# config-bank2.net
KiCad netlist of a schematic drawn in Altium Designer
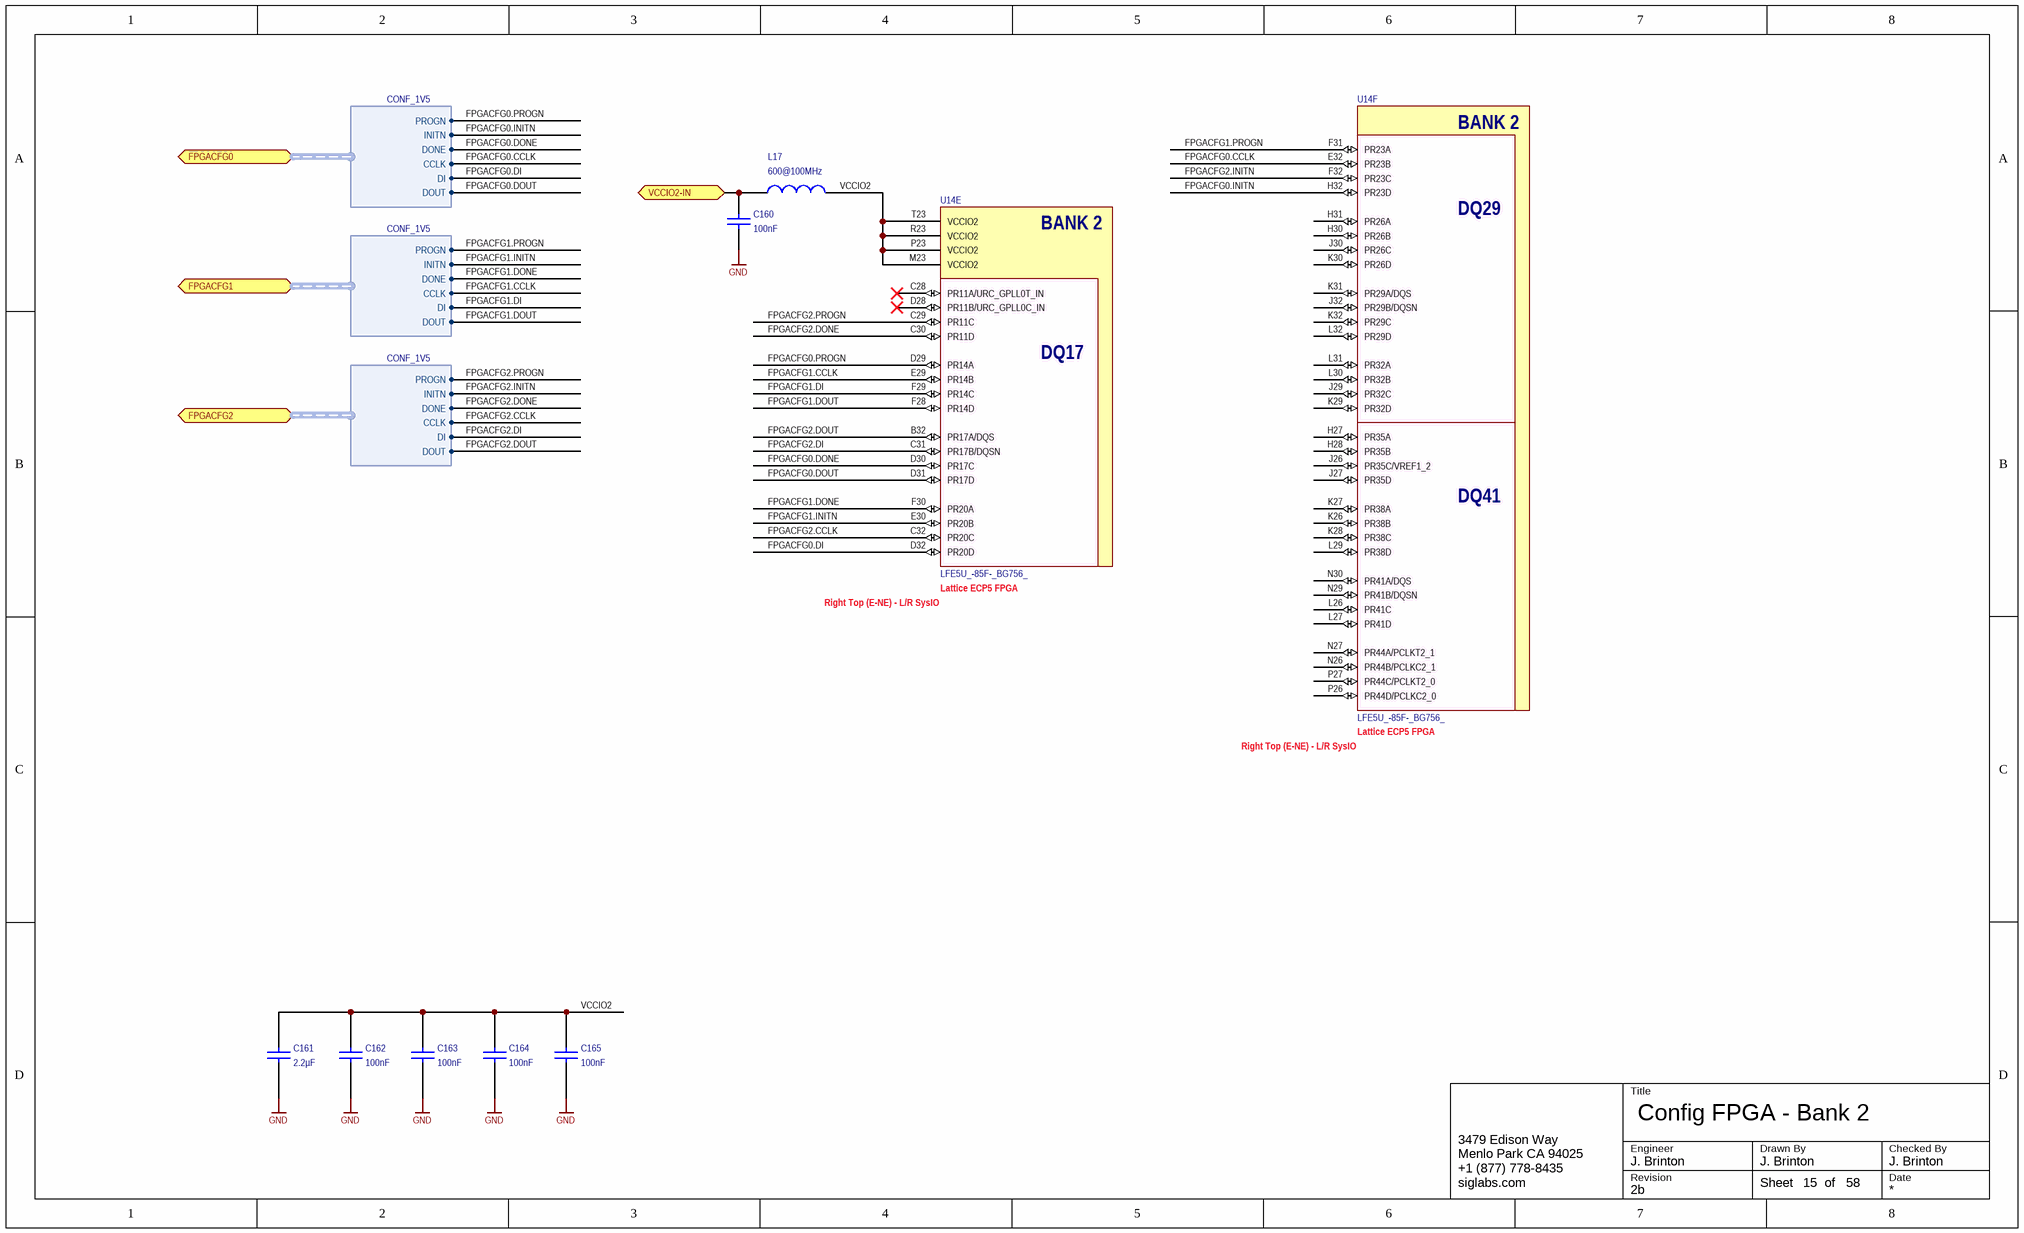
[diagram p0: config-bank2.SchDoc]

(export (version "E")
  (design (tool "Eeschema 10.0.6"))
  (components
    (comp (ref "C160")
      (value "100nF")
      (footprint "generic:CAPC1005X56N")
      (description "Ceramic Capacitor 100nF ±10% 16V X7R 0402")
      (fields (field (name "MANUFACTURER") "Murata") (field (name "TOLERANCE") "±10%"))
      (libsource (lib "murata") (part "GRM155R71A104KA01J"))
    )
    (comp (ref "C161")
      (value "2.2µF")
      (footprint "generic:CAPC1608X90N")
      (description "Ceramic Capacitor 2.2uF ±10% 10V X7R 0603")
      (fields (field (name "MANUFACTURER") "Murata") (field (name "TOLERANCE") "±10%"))
      (libsource (lib "murata") (part "GRM188R71A225KE15D"))
    )
    (comp (ref "C162")
      (value "100nF")
      (footprint "generic:CAPC1005X56N")
      (description "Ceramic Capacitor 100nF ±10% 16V X7R 0402")
      (fields (field (name "MANUFACTURER") "Murata") (field (name "TOLERANCE") "±10%"))
      (libsource (lib "murata") (part "GRM155R71A104KA01J"))
    )
    (comp (ref "C163")
      (value "100nF")
      (footprint "generic:CAPC1005X56N")
      (description "Ceramic Capacitor 100nF ±10% 16V X7R 0402")
      (fields (field (name "MANUFACTURER") "Murata") (field (name "TOLERANCE") "±10%"))
      (libsource (lib "murata") (part "GRM155R71A104KA01J"))
    )
    (comp (ref "C164")
      (value "100nF")
      (footprint "generic:CAPC1005X56N")
      (description "Ceramic Capacitor 100nF ±10% 16V X7R 0402")
      (fields (field (name "MANUFACTURER") "Murata") (field (name "TOLERANCE") "±10%"))
      (libsource (lib "murata") (part "GRM155R71A104KA01J"))
    )
    (comp (ref "C165")
      (value "100nF")
      (footprint "generic:CAPC1005X56N")
      (description "Ceramic Capacitor 100nF ±10% 16V X7R 0402")
      (fields (field (name "MANUFACTURER") "Murata") (field (name "TOLERANCE") "±10%"))
      (libsource (lib "murata") (part "GRM155R71A104KA01J"))
    )
    (comp (ref "L17")
      (value "600@100MHz")
      (footprint "0402")
      (description "Ferrite Bead 600-Ohm @ 100MHz 900mA 0402")
      (fields (field (name "MANUFACTURER") "Murata") (field (name "TOLERANCE") "±25%"))
      (libsource (lib "Graviton") (part "IND 0402"))
    )
    (comp (ref "U14")
      (value "LFE5U_-85F-_BG756_")
      (footprint "lattice:caBGA756")
      (description "ECP5 FPGA, 85k LUT, 756-caBGA")
      (fields (field (name "MANUFACTURER") "Lattice Semiconductor"))
      (libsource (lib "lattice") (part "LFE5U_-85F-_BG756_"))
    )
  )
  (nets
    (net (code "2") (name "/FPGACFG0.CCLK") (class "Default")
      (node (ref "U14") (pin "E32") (pinfunction "PR23B_E32") (pintype "bidirectional"))
    )
    (net (code "3") (name "/FPGACFG0.DI") (class "Default")
      (node (ref "U14") (pin "D32") (pinfunction "PR20D_D32") (pintype "bidirectional"))
    )
    (net (code "4") (name "/FPGACFG0.DONE") (class "Default")
      (node (ref "U14") (pin "D30") (pinfunction "PR17C_D30") (pintype "bidirectional"))
    )
    (net (code "5") (name "/FPGACFG0.DOUT") (class "Default")
      (node (ref "U14") (pin "D31") (pinfunction "PR17D_D31") (pintype "bidirectional"))
    )
    (net (code "6") (name "/FPGACFG0.INITN") (class "Default")
      (node (ref "U14") (pin "H32") (pinfunction "PR23D_H32") (pintype "bidirectional"))
    )
    (net (code "7") (name "/FPGACFG0.PROGN") (class "Default")
      (node (ref "U14") (pin "D29") (pinfunction "PR14A_D29") (pintype "bidirectional"))
    )
    (net (code "8") (name "/FPGACFG1.CCLK") (class "Default")
      (node (ref "U14") (pin "E29") (pinfunction "PR14B_E29") (pintype "bidirectional"))
    )
    (net (code "9") (name "/FPGACFG1.DI") (class "Default")
      (node (ref "U14") (pin "F29") (pinfunction "PR14C_F29") (pintype "bidirectional"))
    )
    (net (code "10") (name "/FPGACFG1.DONE") (class "Default")
      (node (ref "U14") (pin "F30") (pinfunction "PR20A_F30") (pintype "bidirectional"))
    )
    (net (code "11") (name "/FPGACFG1.DOUT") (class "Default")
      (node (ref "U14") (pin "F28") (pinfunction "PR14D_F28") (pintype "bidirectional"))
    )
    (net (code "12") (name "/FPGACFG1.INITN") (class "Default")
      (node (ref "U14") (pin "E30") (pinfunction "PR20B_E30") (pintype "bidirectional"))
    )
    (net (code "13") (name "/FPGACFG1.PROGN") (class "Default")
      (node (ref "U14") (pin "F31") (pinfunction "PR23A_F31") (pintype "bidirectional"))
    )
    (net (code "14") (name "/FPGACFG2.CCLK") (class "Default")
      (node (ref "U14") (pin "C32") (pinfunction "PR20C_C32") (pintype "bidirectional"))
    )
    (net (code "15") (name "/FPGACFG2.DI") (class "Default")
      (node (ref "U14") (pin "C31") (pinfunction "PR17B/DQSN_C31") (pintype "bidirectional"))
    )
    (net (code "16") (name "/FPGACFG2.DONE") (class "Default")
      (node (ref "U14") (pin "C30") (pinfunction "PR11D_C30") (pintype "bidirectional"))
    )
    (net (code "17") (name "/FPGACFG2.DOUT") (class "Default")
      (node (ref "U14") (pin "B32") (pinfunction "PR17A/DQS_B32") (pintype "bidirectional"))
    )
    (net (code "18") (name "/FPGACFG2.INITN") (class "Default")
      (node (ref "U14") (pin "F32") (pinfunction "PR23C_F32") (pintype "bidirectional"))
    )
    (net (code "19") (name "/FPGACFG2.PROGN") (class "Default")
      (node (ref "U14") (pin "C29") (pinfunction "PR11C_C29") (pintype "bidirectional"))
    )
    (net (code "20") (name "/VCCIO2") (class "Default")
      (node (ref "C161") (pin "2") (pinfunction "2_2") (pintype "passive"))
      (node (ref "C162") (pin "2") (pinfunction "2_2") (pintype "passive"))
      (node (ref "C163") (pin "2") (pinfunction "2_2") (pintype "passive"))
      (node (ref "C164") (pin "2") (pinfunction "2_2") (pintype "passive"))
      (node (ref "C165") (pin "2") (pinfunction "2_2") (pintype "passive"))
      (node (ref "L17") (pin "1") (pinfunction "1_1") (pintype "passive"))
      (node (ref "U14") (pin "M23") (pinfunction "VCCIO2_M23") (pintype "power_in"))
      (node (ref "U14") (pin "P23") (pinfunction "VCCIO2_P23") (pintype "power_in"))
      (node (ref "U14") (pin "R23") (pinfunction "VCCIO2_R23") (pintype "power_in"))
      (node (ref "U14") (pin "T23") (pinfunction "VCCIO2_T23") (pintype "power_in"))
    )
    (net (code "21") (name "/VCCIO2-IN") (class "Default")
      (node (ref "C160") (pin "2") (pinfunction "2_2") (pintype "passive"))
      (node (ref "L17") (pin "2") (pinfunction "2_2") (pintype "passive"))
    )
    (net (code "23") (name "GND") (class "Default")
      (node (ref "C160") (pin "1") (pinfunction "1_1") (pintype "passive"))
      (node (ref "C161") (pin "1") (pinfunction "1_1") (pintype "passive"))
      (node (ref "C162") (pin "1") (pinfunction "1_1") (pintype "passive"))
      (node (ref "C163") (pin "1") (pinfunction "1_1") (pintype "passive"))
      (node (ref "C164") (pin "1") (pinfunction "1_1") (pintype "passive"))
      (node (ref "C165") (pin "1") (pinfunction "1_1") (pintype "passive"))
    )
    (net (code "24") (name "unconnected-(U14E-PR11A{slash}URC_GPLL0T_IN-PadC28)") (class "Default")
      (node (ref "U14") (pin "C28") (pinfunction "PR11A/URC_GPLL0T_IN_C28") (pintype "bidirectional+no_connect"))
    )
    (net (code "25") (name "unconnected-(U14E-PR11B{slash}URC_GPLL0C_IN-PadD28)") (class "Default")
      (node (ref "U14") (pin "D28") (pinfunction "PR11B/URC_GPLL0C_IN_D28") (pintype "bidirectional+no_connect"))
    )
    (net (code "26") (name "unconnected-(U14F-PR26A-PadH31)") (class "Default")
      (node (ref "U14") (pin "H31") (pinfunction "PR26A_H31") (pintype "bidirectional"))
    )
    (net (code "27") (name "unconnected-(U14F-PR26B-PadH30)") (class "Default")
      (node (ref "U14") (pin "H30") (pinfunction "PR26B_H30") (pintype "bidirectional"))
    )
    (net (code "28") (name "unconnected-(U14F-PR26C-PadJ30)") (class "Default")
      (node (ref "U14") (pin "J30") (pinfunction "PR26C_J30") (pintype "bidirectional"))
    )
    (net (code "29") (name "unconnected-(U14F-PR26D-PadK30)") (class "Default")
      (node (ref "U14") (pin "K30") (pinfunction "PR26D_K30") (pintype "bidirectional"))
    )
    (net (code "30") (name "unconnected-(U14F-PR29A{slash}DQS-PadK31)") (class "Default")
      (node (ref "U14") (pin "K31") (pinfunction "PR29A/DQS_K31") (pintype "bidirectional"))
    )
    (net (code "31") (name "unconnected-(U14F-PR29B{slash}DQSN-PadJ32)") (class "Default")
      (node (ref "U14") (pin "J32") (pinfunction "PR29B/DQSN_J32") (pintype "bidirectional"))
    )
    (net (code "32") (name "unconnected-(U14F-PR29C-PadK32)") (class "Default")
      (node (ref "U14") (pin "K32") (pinfunction "PR29C_K32") (pintype "bidirectional"))
    )
    (net (code "33") (name "unconnected-(U14F-PR29D-PadL32)") (class "Default")
      (node (ref "U14") (pin "L32") (pinfunction "PR29D_L32") (pintype "bidirectional"))
    )
    (net (code "34") (name "unconnected-(U14F-PR32A-PadL31)") (class "Default")
      (node (ref "U14") (pin "L31") (pinfunction "PR32A_L31") (pintype "bidirectional"))
    )
    (net (code "35") (name "unconnected-(U14F-PR32B-PadL30)") (class "Default")
      (node (ref "U14") (pin "L30") (pinfunction "PR32B_L30") (pintype "bidirectional"))
    )
    (net (code "36") (name "unconnected-(U14F-PR32C-PadJ29)") (class "Default")
      (node (ref "U14") (pin "J29") (pinfunction "PR32C_J29") (pintype "bidirectional"))
    )
    (net (code "37") (name "unconnected-(U14F-PR32D-PadK29)") (class "Default")
      (node (ref "U14") (pin "K29") (pinfunction "PR32D_K29") (pintype "bidirectional"))
    )
    (net (code "38") (name "unconnected-(U14F-PR35A-PadH27)") (class "Default")
      (node (ref "U14") (pin "H27") (pinfunction "PR35A_H27") (pintype "bidirectional"))
    )
    (net (code "39") (name "unconnected-(U14F-PR35B-PadH28)") (class "Default")
      (node (ref "U14") (pin "H28") (pinfunction "PR35B_H28") (pintype "bidirectional"))
    )
    (net (code "40") (name "unconnected-(U14F-PR35C{slash}VREF1_2-PadJ26)") (class "Default")
      (node (ref "U14") (pin "J26") (pinfunction "PR35C/VREF1_2_J26") (pintype "bidirectional"))
    )
    (net (code "41") (name "unconnected-(U14F-PR35D-PadJ27)") (class "Default")
      (node (ref "U14") (pin "J27") (pinfunction "PR35D_J27") (pintype "bidirectional"))
    )
    (net (code "42") (name "unconnected-(U14F-PR38A-PadK27)") (class "Default")
      (node (ref "U14") (pin "K27") (pinfunction "PR38A_K27") (pintype "bidirectional"))
    )
    (net (code "43") (name "unconnected-(U14F-PR38B-PadK26)") (class "Default")
      (node (ref "U14") (pin "K26") (pinfunction "PR38B_K26") (pintype "bidirectional"))
    )
    (net (code "44") (name "unconnected-(U14F-PR38C-PadK28)") (class "Default")
      (node (ref "U14") (pin "K28") (pinfunction "PR38C_K28") (pintype "bidirectional"))
    )
    (net (code "45") (name "unconnected-(U14F-PR38D-PadL29)") (class "Default")
      (node (ref "U14") (pin "L29") (pinfunction "PR38D_L29") (pintype "bidirectional"))
    )
    (net (code "46") (name "unconnected-(U14F-PR41A{slash}DQS-PadN30)") (class "Default")
      (node (ref "U14") (pin "N30") (pinfunction "PR41A/DQS_N30") (pintype "bidirectional"))
    )
    (net (code "47") (name "unconnected-(U14F-PR41B{slash}DQSN-PadN29)") (class "Default")
      (node (ref "U14") (pin "N29") (pinfunction "PR41B/DQSN_N29") (pintype "bidirectional"))
    )
    (net (code "48") (name "unconnected-(U14F-PR41C-PadL26)") (class "Default")
      (node (ref "U14") (pin "L26") (pinfunction "PR41C_L26") (pintype "bidirectional"))
    )
    (net (code "49") (name "unconnected-(U14F-PR41D-PadL27)") (class "Default")
      (node (ref "U14") (pin "L27") (pinfunction "PR41D_L27") (pintype "bidirectional"))
    )
    (net (code "50") (name "unconnected-(U14F-PR44A{slash}PCLKT2_1-PadN27)") (class "Default")
      (node (ref "U14") (pin "N27") (pinfunction "PR44A/PCLKT2_1_N27") (pintype "bidirectional"))
    )
    (net (code "51") (name "unconnected-(U14F-PR44B{slash}PCLKC2_1-PadN26)") (class "Default")
      (node (ref "U14") (pin "N26") (pinfunction "PR44B/PCLKC2_1_N26") (pintype "bidirectional"))
    )
    (net (code "52") (name "unconnected-(U14F-PR44C{slash}PCLKT2_0-PadP27)") (class "Default")
      (node (ref "U14") (pin "P27") (pinfunction "PR44C/PCLKT2_0_P27") (pintype "bidirectional"))
    )
    (net (code "53") (name "unconnected-(U14F-PR44D{slash}PCLKC2_0-PadP26)") (class "Default")
      (node (ref "U14") (pin "P26") (pinfunction "PR44D/PCLKC2_0_P26") (pintype "bidirectional"))
    )
  )
)
